# acoplador_50_50.net
KiCad netlist of a schematic drawn in Altium Designer
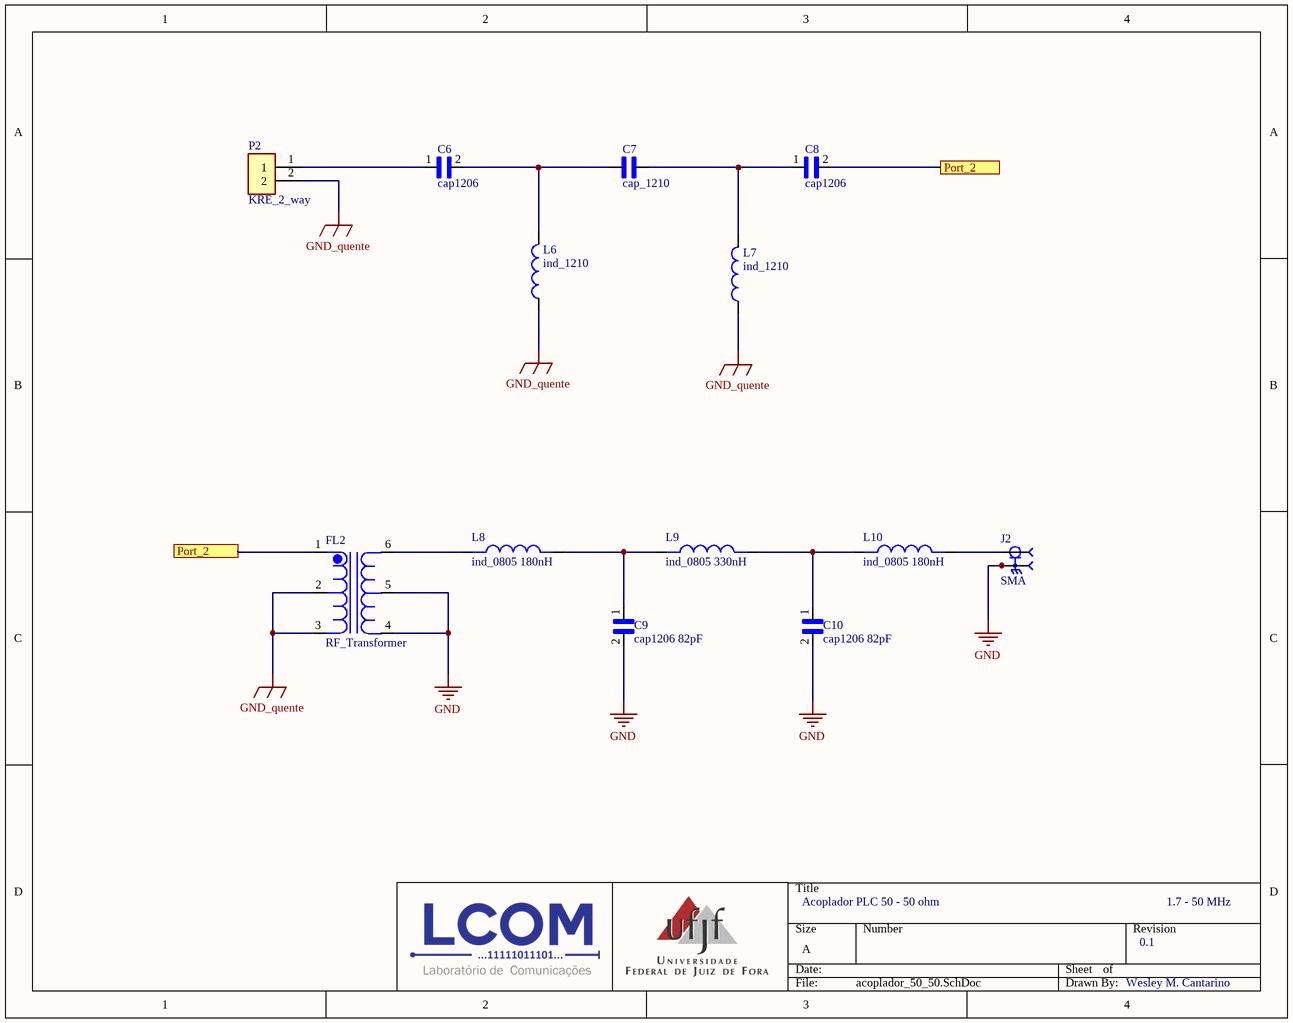
[diagram p0: acoplador_50_50.SchDoc]

(export (version "E")
  (design (tool "Eeschema 10.0.6"))
  (components
    (comp (ref "C6")
      (value "cap1206")
      (footprint "CAPC3216X160N")
      (fields (field (name "MF") "{'manufacturer': u'Syfer'}") (field (name "MP") "1206J2K00820JCT"))
      (libsource (lib "") (part "cap1206_1"))
    )
    (comp (ref "C7")
      (value "cap_1210")
      (footprint "CAPC3225X200N")
      (fields
        (field (name "MF") "{'manufacturer': u'Murata Electronics'}")
        (field (name "MP") "GR332DD72J333KW01L")
      )
      (libsource (lib "Integrated_Library") (part "cap_1210"))
    )
    (comp (ref "C8")
      (value "cap1206")
      (footprint "CAPC3216X160N")
      (fields (field (name "MF") "{'manufacturer': u'Syfer'}") (field (name "MP") "1206J2K00820JCT"))
      (libsource (lib "") (part "cap1206_1"))
    )
    (comp (ref "C9")
      (value "cap1206 82pF")
      (footprint "CAPC3216X160N")
      (fields (field (name "MF") "{'manufacturer': u'Syfer'}") (field (name "MP") "1206J2K00820JCT"))
      (libsource (lib "Integrated_Library") (part "cap1206"))
    )
    (comp (ref "C10")
      (value "cap1206 82pF")
      (footprint "CAPC3216X160N")
      (fields (field (name "MF") "{'manufacturer': u'Syfer'}") (field (name "MP") "1206J2K00820JCT"))
      (libsource (lib "Integrated_Library") (part "cap1206"))
    )
    (comp (ref "FL2")
      (value "RF_Transformer")
      (footprint "FIL_KA4909-AL")
      (description "Bias Injection Choke PWB 1.5 AL 30k 300M 1:1.5")
      (fields (field (name "MF") "{'manufacturer': u'Coilcraft'}") (field (name "MP") "KA4909-AL"))
      (libsource (lib "Integrated_Library") (part "RF_Transformer"))
    )
    (comp (ref "J2")
      (value "SMA")
      (footprint "JOHNSON_142-0701-201")
      (description "Johnson Components 142-0701-201 / Conn Recept Straight Pcb .155\"\"")
      (fields
        (field (name "MF") "{'manufacturer': u'Cinch Connectivity Solutions Johnson'}")
        (field (name "MP") "142-0701-201")
      )
      (libsource (lib "Integrated_Library") (part "SMA"))
    )
    (comp (ref "L6")
      (value "ind_1210")
      (footprint "INDC3225X120N")
      (description "Ind Metal Alloy Shielded 1.5uH 20% 1MHz Powdered Iron 2.6A 1210 T/R")
      (fields
        (field (name "MP") "1277AS-H-1R5M=P2")
        (field (name "MF") "{'manufacturer': u'Murata Electronics'}")
      )
      (libsource (lib "Integrated_Library") (part "ind_1210"))
    )
    (comp (ref "L7")
      (value "ind_1210")
      (footprint "INDC3225X120N")
      (description "Ind Metal Alloy Shielded 1.5uH 20% 1MHz Powdered Iron 2.6A 1210 T/R")
      (fields
        (field (name "MP") "1277AS-H-1R5M=P2")
        (field (name "MF") "{'manufacturer': u'Murata Electronics'}")
      )
      (libsource (lib "Integrated_Library") (part "ind_1210"))
    )
    (comp (ref "L8")
      (value "ind_0805 180nH")
      (footprint "IND_ASMCI-0805-4R7M-T")
      (fields (field (name "MF") "{'manufacturer': u'Abracon'}") (field (name "MP") "ASMCI-0805-4R7M-T"))
      (libsource (lib "Integrated_Library") (part "ind_0805"))
    )
    (comp (ref "L9")
      (value "ind_0805 330nH")
      (footprint "IND_ASMCI-0805-4R7M-T")
      (fields (field (name "MF") "{'manufacturer': u'Abracon'}") (field (name "MP") "ASMCI-0805-4R7M-T"))
      (libsource (lib "Integrated_Library") (part "ind_0805"))
    )
    (comp (ref "L10")
      (value "ind_0805 180nH")
      (footprint "IND_ASMCI-0805-4R7M-T")
      (fields (field (name "MF") "{'manufacturer': u'Abracon'}") (field (name "MP") "ASMCI-0805-4R7M-T"))
      (libsource (lib "Integrated_Library") (part "ind_0805"))
    )
    (comp (ref "P2")
      (value "KRE_2_way")
      (footprint "TE_282837-2")
      (description "TERM BLOCK 5.08MM 2POS SIDE ENTY")
      (fields (field (name "MP") "282837-2") (field (name "MF") "{'manufacturer': u'TE Connectivity'}"))
      (libsource (lib "Integrated_Library") (part "KRE_2_way"))
    )
  )
  (nets
    (net (code "1") (name "/Port_2") (class "Default")
      (node (ref "C8") (pin "2") (pinfunction "2_2") (pintype "passive"))
      (node (ref "FL2") (pin "1") (pinfunction "1_1") (pintype "passive"))
    )
    (net (code "2") (name "GND") (class "Default")
      (node (ref "C10") (pin "2") (pinfunction "2_2") (pintype "passive"))
      (node (ref "C9") (pin "2") (pinfunction "2_2") (pintype "passive"))
      (node (ref "FL2") (pin "4") (pinfunction "4_4") (pintype "passive"))
      (node (ref "FL2") (pin "5") (pinfunction "5_5") (pintype "passive"))
      (node (ref "J2") (pin "2") (pinfunction "2_2") (pintype "passive"))
      (node (ref "J2") (pin "3") (pinfunction "2_3") (pintype "passive"))
      (node (ref "J2") (pin "4") (pinfunction "2_4") (pintype "passive"))
      (node (ref "J2") (pin "5") (pinfunction "2_5") (pintype "passive"))
    )
    (net (code "3") (name "GND_quente") (class "Default")
      (node (ref "FL2") (pin "2") (pinfunction "2_2") (pintype "passive"))
      (node (ref "FL2") (pin "3") (pinfunction "3_3") (pintype "passive"))
      (node (ref "L6") (pin "1") (pinfunction "1_1") (pintype "passive"))
      (node (ref "L7") (pin "1") (pinfunction "1_1") (pintype "passive"))
      (node (ref "P2") (pin "2") (pinfunction "2_2") (pintype "passive"))
    )
    (net (code "4") (name "Net-(C6-Pad1)") (class "Default")
      (node (ref "C6") (pin "1") (pinfunction "1_1") (pintype "passive"))
      (node (ref "P2") (pin "1") (pinfunction "1_1") (pintype "passive"))
    )
    (net (code "5") (name "Net-(C6-Pad2)") (class "Default")
      (node (ref "C6") (pin "2") (pinfunction "2_2") (pintype "passive"))
      (node (ref "C7") (pin "1") (pinfunction "1_1") (pintype "passive"))
      (node (ref "L6") (pin "2") (pinfunction "2_2") (pintype "passive"))
    )
    (net (code "6") (name "Net-(C7-Pad2)") (class "Default")
      (node (ref "C7") (pin "2") (pinfunction "2_2") (pintype "passive"))
      (node (ref "C8") (pin "1") (pinfunction "1_1") (pintype "passive"))
      (node (ref "L7") (pin "2") (pinfunction "2_2") (pintype "passive"))
    )
    (net (code "7") (name "Net-(C9-Pad1)") (class "Default")
      (node (ref "C9") (pin "1") (pinfunction "1_1") (pintype "passive"))
      (node (ref "L8") (pin "2") (pinfunction "2_2") (pintype "passive"))
      (node (ref "L9") (pin "1") (pinfunction "1_1") (pintype "passive"))
    )
    (net (code "8") (name "Net-(C10-Pad1)") (class "Default")
      (node (ref "C10") (pin "1") (pinfunction "1_1") (pintype "passive"))
      (node (ref "L10") (pin "1") (pinfunction "1_1") (pintype "passive"))
      (node (ref "L9") (pin "2") (pinfunction "2_2") (pintype "passive"))
    )
    (net (code "9") (name "Net-(FL2-Pad6)") (class "Default")
      (node (ref "FL2") (pin "6") (pinfunction "6_6") (pintype "passive"))
      (node (ref "L8") (pin "1") (pinfunction "1_1") (pintype "passive"))
    )
    (net (code "10") (name "Net-(J2-Pad1)") (class "Default")
      (node (ref "J2") (pin "1") (pinfunction "1_1") (pintype "passive"))
      (node (ref "L10") (pin "2") (pinfunction "2_2") (pintype "passive"))
    )
  )
)
